# Shim_IWM.net
KiCad netlist of a schematic drawn in EAGLE
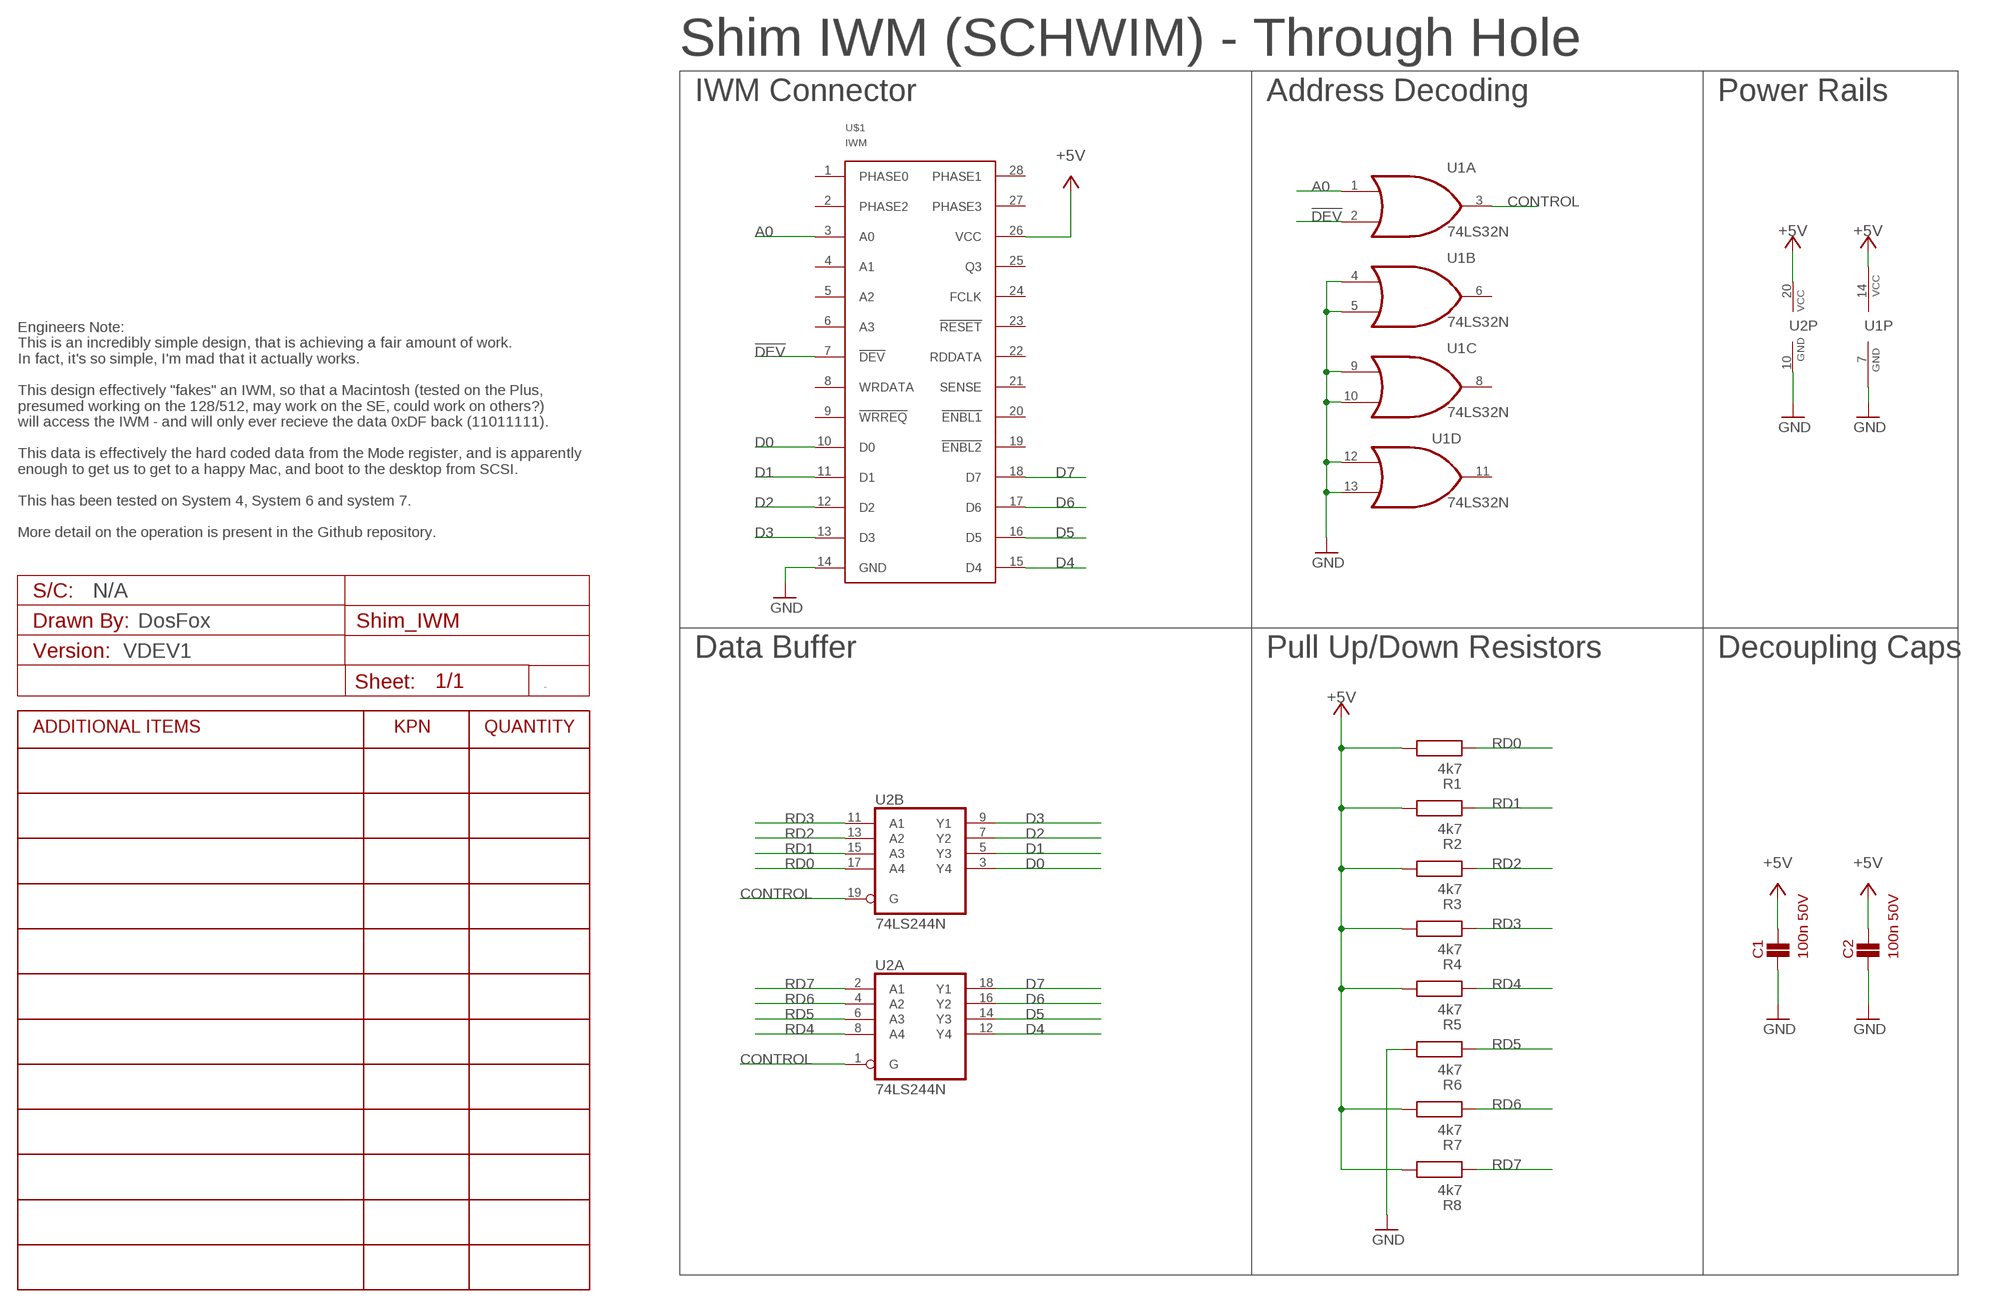
[diagram p0: schematic, sheet 1]

(export (version "E")
  (design (tool "Eeschema 10.0.6"))
  (components
    (comp (ref "A1")
      (value "VDEV1")
      (footprint "eagle-import:PCB_CUSTOM_DETAILS")
      (libsource (lib "eagle-import") (part "PROJECT_DETAILS_CUSTOM"))
    )
    (comp (ref "C1")
      (value "100n 50V")
      (footprint "eagle-import:CAP_5.08MM_PITCH")
      (libsource (lib "eagle-import") (part "100N_TH_CAP"))
    )
    (comp (ref "C2")
      (value "100n 50V")
      (footprint "eagle-import:CAP_5.08MM_PITCH")
      (libsource (lib "eagle-import") (part "100N_TH_CAP"))
    )
    (comp (ref "R1")
      (value "4k7")
      (footprint "eagle-import:RESISTORTHRUHOLE")
      (libsource (lib "eagle-import") (part "4K7_TH_RESISTOR"))
    )
    (comp (ref "R2")
      (value "4k7")
      (footprint "eagle-import:RESISTORTHRUHOLE")
      (libsource (lib "eagle-import") (part "4K7_TH_RESISTOR"))
    )
    (comp (ref "R3")
      (value "4k7")
      (footprint "eagle-import:RESISTORTHRUHOLE")
      (libsource (lib "eagle-import") (part "4K7_TH_RESISTOR"))
    )
    (comp (ref "R4")
      (value "4k7")
      (footprint "eagle-import:RESISTORTHRUHOLE")
      (libsource (lib "eagle-import") (part "4K7_TH_RESISTOR"))
    )
    (comp (ref "R5")
      (value "4k7")
      (footprint "eagle-import:RESISTORTHRUHOLE")
      (libsource (lib "eagle-import") (part "4K7_TH_RESISTOR"))
    )
    (comp (ref "R6")
      (value "4k7")
      (footprint "eagle-import:RESISTORTHRUHOLE")
      (libsource (lib "eagle-import") (part "4K7_TH_RESISTOR"))
    )
    (comp (ref "R7")
      (value "4k7")
      (footprint "eagle-import:RESISTORTHRUHOLE")
      (libsource (lib "eagle-import") (part "4K7_TH_RESISTOR"))
    )
    (comp (ref "R8")
      (value "4k7")
      (footprint "eagle-import:RESISTORTHRUHOLE")
      (libsource (lib "eagle-import") (part "4K7_TH_RESISTOR"))
    )
    (comp (ref "U$1")
      (value "IWM")
      (footprint "eagle-import:DIP28")
      (libsource (lib "eagle-import") (part "IWM"))
    )
    (comp (ref "U1")
      (value "74LS32N")
      (footprint "eagle-import:DIL14")
      (libsource (lib "eagle-import") (part "7432NLS"))
    )
    (comp (ref "U2")
      (value "74LS244N")
      (footprint "eagle-import:DIL20")
      (libsource (lib "eagle-import") (part "74244NLS"))
    )
  )
  (nets
    (net (code "1") (name "/A0") (class "Default")
      (node (ref "U$1") (pin "3") (pinfunction "A0_3") (pintype "bidirectional"))
      (node (ref "U1") (pin "1") (pinfunction "I0_1") (pintype "input"))
    )
    (net (code "2") (name "/CONTROL") (class "Default")
      (node (ref "U1") (pin "3") (pinfunction "O_3") (pintype "output"))
      (node (ref "U2") (pin "1") (pinfunction "G_1") (pintype "input"))
      (node (ref "U2") (pin "19") (pinfunction "G_19") (pintype "input"))
    )
    (net (code "3") (name "/D0") (class "Default")
      (node (ref "U$1") (pin "10") (pinfunction "D0_10") (pintype "bidirectional"))
      (node (ref "U2") (pin "3") (pinfunction "Y4_3") (pintype "tri_state"))
    )
    (net (code "4") (name "/D1") (class "Default")
      (node (ref "U$1") (pin "11") (pinfunction "D1_11") (pintype "bidirectional"))
      (node (ref "U2") (pin "5") (pinfunction "Y3_5") (pintype "tri_state"))
    )
    (net (code "5") (name "/D2") (class "Default")
      (node (ref "U$1") (pin "12") (pinfunction "D2_12") (pintype "bidirectional"))
      (node (ref "U2") (pin "7") (pinfunction "Y2_7") (pintype "tri_state"))
    )
    (net (code "6") (name "/D3") (class "Default")
      (node (ref "U$1") (pin "13") (pinfunction "D3_13") (pintype "bidirectional"))
      (node (ref "U2") (pin "9") (pinfunction "Y1_9") (pintype "tri_state"))
    )
    (net (code "7") (name "/D4") (class "Default")
      (node (ref "U$1") (pin "15") (pinfunction "D4_15") (pintype "bidirectional"))
      (node (ref "U2") (pin "12") (pinfunction "Y4_12") (pintype "tri_state"))
    )
    (net (code "8") (name "/D5") (class "Default")
      (node (ref "U$1") (pin "16") (pinfunction "D5_16") (pintype "bidirectional"))
      (node (ref "U2") (pin "14") (pinfunction "Y3_14") (pintype "tri_state"))
    )
    (net (code "9") (name "/D6") (class "Default")
      (node (ref "U$1") (pin "17") (pinfunction "D6_17") (pintype "bidirectional"))
      (node (ref "U2") (pin "16") (pinfunction "Y2_16") (pintype "tri_state"))
    )
    (net (code "10") (name "/D7") (class "Default")
      (node (ref "U$1") (pin "18") (pinfunction "D7_18") (pintype "bidirectional"))
      (node (ref "U2") (pin "18") (pinfunction "Y1_18") (pintype "tri_state"))
    )
    (net (code "11") (name "/RD0") (class "Default")
      (node (ref "R1") (pin "P$1") (pinfunction "P$1_P$1") (pintype "bidirectional"))
      (node (ref "U2") (pin "17") (pinfunction "A4_17") (pintype "input"))
    )
    (net (code "12") (name "/RD1") (class "Default")
      (node (ref "R2") (pin "P$1") (pinfunction "P$1_P$1") (pintype "bidirectional"))
      (node (ref "U2") (pin "15") (pinfunction "A3_15") (pintype "input"))
    )
    (net (code "13") (name "/RD2") (class "Default")
      (node (ref "R3") (pin "P$1") (pinfunction "P$1_P$1") (pintype "bidirectional"))
      (node (ref "U2") (pin "13") (pinfunction "A2_13") (pintype "input"))
    )
    (net (code "14") (name "/RD3") (class "Default")
      (node (ref "R4") (pin "P$1") (pinfunction "P$1_P$1") (pintype "bidirectional"))
      (node (ref "U2") (pin "11") (pinfunction "A1_11") (pintype "input"))
    )
    (net (code "15") (name "/RD4") (class "Default")
      (node (ref "R5") (pin "P$1") (pinfunction "P$1_P$1") (pintype "bidirectional"))
      (node (ref "U2") (pin "8") (pinfunction "A4_8") (pintype "input"))
    )
    (net (code "16") (name "/RD5") (class "Default")
      (node (ref "R6") (pin "P$1") (pinfunction "P$1_P$1") (pintype "bidirectional"))
      (node (ref "U2") (pin "6") (pinfunction "A3_6") (pintype "input"))
    )
    (net (code "17") (name "/RD6") (class "Default")
      (node (ref "R7") (pin "P$1") (pinfunction "P$1_P$1") (pintype "bidirectional"))
      (node (ref "U2") (pin "4") (pinfunction "A2_4") (pintype "input"))
    )
    (net (code "18") (name "/RD7") (class "Default")
      (node (ref "R8") (pin "P$1") (pinfunction "P$1_P$1") (pintype "bidirectional"))
      (node (ref "U2") (pin "2") (pinfunction "A1_2") (pintype "input"))
    )
    (net (code "19") (name "/~{DEV}") (class "Default")
      (node (ref "U$1") (pin "7") (pinfunction "~{DEV}_7") (pintype "bidirectional"))
      (node (ref "U1") (pin "2") (pinfunction "I1_2") (pintype "input"))
    )
    (net (code "20") (name "GND") (class "Default")
      (node (ref "C1") (pin "P$1") (pinfunction "P$1_P$1") (pintype "bidirectional"))
      (node (ref "C2") (pin "P$1") (pinfunction "P$1_P$1") (pintype "bidirectional"))
      (node (ref "R6") (pin "P$2") (pinfunction "P$2_P$2") (pintype "bidirectional"))
      (node (ref "U$1") (pin "14") (pinfunction "GND_14") (pintype "bidirectional"))
      (node (ref "U1") (pin "10") (pinfunction "I1_10") (pintype "input"))
      (node (ref "U1") (pin "12") (pinfunction "I0_12") (pintype "input"))
      (node (ref "U1") (pin "13") (pinfunction "I1_13") (pintype "input"))
      (node (ref "U1") (pin "4") (pinfunction "I0_4") (pintype "input"))
      (node (ref "U1") (pin "5") (pinfunction "I1_5") (pintype "input"))
      (node (ref "U1") (pin "7") (pinfunction "GND_7") (pintype "power_in"))
      (node (ref "U1") (pin "9") (pinfunction "I0_9") (pintype "input"))
      (node (ref "U2") (pin "10") (pinfunction "GND_10") (pintype "power_in"))
    )
    (net (code "21") (name "VCC") (class "Default")
      (node (ref "C1") (pin "P$2") (pinfunction "P$2_P$2") (pintype "bidirectional"))
      (node (ref "C2") (pin "P$2") (pinfunction "P$2_P$2") (pintype "bidirectional"))
      (node (ref "R1") (pin "P$2") (pinfunction "P$2_P$2") (pintype "bidirectional"))
      (node (ref "R2") (pin "P$2") (pinfunction "P$2_P$2") (pintype "bidirectional"))
      (node (ref "R3") (pin "P$2") (pinfunction "P$2_P$2") (pintype "bidirectional"))
      (node (ref "R4") (pin "P$2") (pinfunction "P$2_P$2") (pintype "bidirectional"))
      (node (ref "R5") (pin "P$2") (pinfunction "P$2_P$2") (pintype "bidirectional"))
      (node (ref "R7") (pin "P$2") (pinfunction "P$2_P$2") (pintype "bidirectional"))
      (node (ref "R8") (pin "P$2") (pinfunction "P$2_P$2") (pintype "bidirectional"))
      (node (ref "U$1") (pin "26") (pinfunction "VCC_26") (pintype "bidirectional"))
      (node (ref "U1") (pin "14") (pinfunction "VCC_14") (pintype "power_in"))
      (node (ref "U2") (pin "20") (pinfunction "VCC_20") (pintype "power_in"))
    )
    (net (code "22") (name "unconnected-(U$1-A1-Pad4)") (class "Default")
      (node (ref "U$1") (pin "4") (pinfunction "A1_4") (pintype "bidirectional"))
    )
    (net (code "23") (name "unconnected-(U$1-A2-Pad5)") (class "Default")
      (node (ref "U$1") (pin "5") (pinfunction "A2_5") (pintype "bidirectional"))
    )
    (net (code "24") (name "unconnected-(U$1-A3-Pad6)") (class "Default")
      (node (ref "U$1") (pin "6") (pinfunction "A3_6") (pintype "bidirectional"))
    )
    (net (code "25") (name "unconnected-(U$1-FCLK-Pad24)") (class "Default")
      (node (ref "U$1") (pin "24") (pinfunction "FCLK_24") (pintype "bidirectional"))
    )
    (net (code "26") (name "unconnected-(U$1-PHASE0-Pad1)") (class "Default")
      (node (ref "U$1") (pin "1") (pinfunction "PHASE0_1") (pintype "bidirectional"))
    )
    (net (code "27") (name "unconnected-(U$1-PHASE1-Pad28)") (class "Default")
      (node (ref "U$1") (pin "28") (pinfunction "PHASE1_28") (pintype "bidirectional"))
    )
    (net (code "28") (name "unconnected-(U$1-PHASE2-Pad2)") (class "Default")
      (node (ref "U$1") (pin "2") (pinfunction "PHASE2_2") (pintype "bidirectional"))
    )
    (net (code "29") (name "unconnected-(U$1-PHASE3-Pad27)") (class "Default")
      (node (ref "U$1") (pin "27") (pinfunction "PHASE3_27") (pintype "bidirectional"))
    )
    (net (code "30") (name "unconnected-(U$1-Q3-Pad25)") (class "Default")
      (node (ref "U$1") (pin "25") (pinfunction "Q3_25") (pintype "bidirectional"))
    )
    (net (code "31") (name "unconnected-(U$1-RDDATA-Pad22)") (class "Default")
      (node (ref "U$1") (pin "22") (pinfunction "RDDATA_22") (pintype "bidirectional"))
    )
    (net (code "32") (name "unconnected-(U$1-SENSE-Pad21)") (class "Default")
      (node (ref "U$1") (pin "21") (pinfunction "SENSE_21") (pintype "bidirectional"))
    )
    (net (code "33") (name "unconnected-(U$1-WRDATA-Pad8)") (class "Default")
      (node (ref "U$1") (pin "8") (pinfunction "WRDATA_8") (pintype "bidirectional"))
    )
    (net (code "34") (name "unconnected-(U$1-~{ENBL1}-Pad20)") (class "Default")
      (node (ref "U$1") (pin "20") (pinfunction "~{ENBL1}_20") (pintype "bidirectional"))
    )
    (net (code "35") (name "unconnected-(U$1-~{ENBL2}-Pad19)") (class "Default")
      (node (ref "U$1") (pin "19") (pinfunction "~{ENBL2}_19") (pintype "bidirectional"))
    )
    (net (code "36") (name "unconnected-(U$1-~{RESET}-Pad23)") (class "Default")
      (node (ref "U$1") (pin "23") (pinfunction "~{RESET}_23") (pintype "bidirectional"))
    )
    (net (code "37") (name "unconnected-(U$1-~{WRREQ}-Pad9)") (class "Default")
      (node (ref "U$1") (pin "9") (pinfunction "~{WRREQ}_9") (pintype "bidirectional"))
    )
    (net (code "38") (name "unconnected-(U1B-O-Pad6)") (class "Default")
      (node (ref "U1") (pin "6") (pinfunction "O_6") (pintype "output"))
    )
    (net (code "39") (name "unconnected-(U1C-O-Pad8)") (class "Default")
      (node (ref "U1") (pin "8") (pinfunction "O_8") (pintype "output"))
    )
    (net (code "40") (name "unconnected-(U1D-O-Pad11)") (class "Default")
      (node (ref "U1") (pin "11") (pinfunction "O_11") (pintype "output"))
    )
  )
)
